# contact.net
KiCad netlist of a schematic drawn in EAGLE
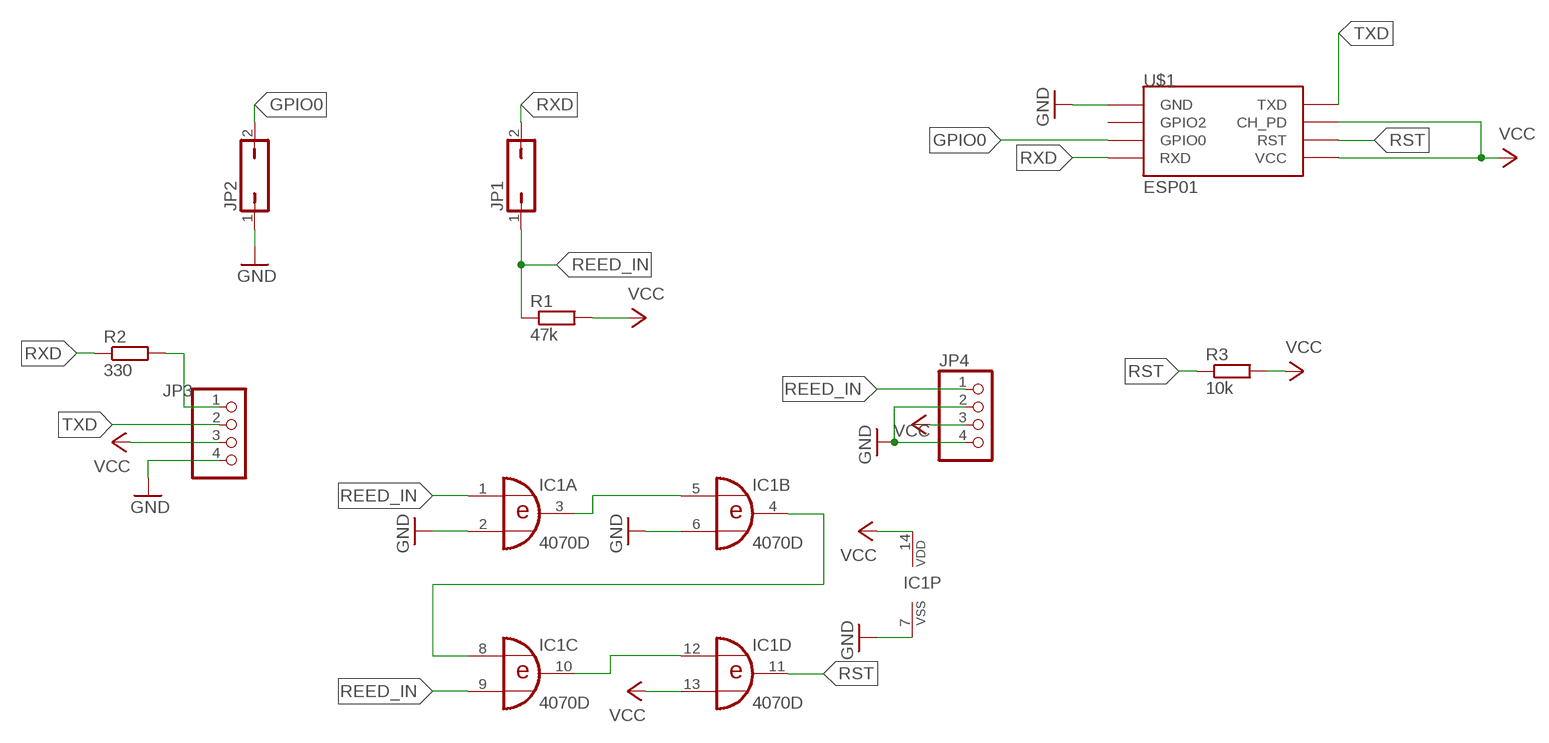
[diagram p0: schematic, sheet 1]

(export (version "E")
  (design (tool "Eeschema 10.0.6"))
  (components
    (comp (ref "IC1")
      (value "4070D")
      (footprint "eagle-import:SO14")
      (libsource (lib "eagle-import") (part "4070D"))
    )
    (comp (ref "JP1")
      (value "JP1Q")
      (footprint "eagle-import:JP1")
      (libsource (lib "eagle-import") (part "JP1Q"))
    )
    (comp (ref "JP2")
      (value "JP1Q")
      (footprint "eagle-import:JP1")
      (libsource (lib "eagle-import") (part "JP1Q"))
    )
    (comp (ref "JP3")
      (value "PINHD-1X4")
      (footprint "eagle-import:1X04")
      (libsource (lib "eagle-import") (part "PINHD-1X4"))
    )
    (comp (ref "JP4")
      (value "PINHD-1X4")
      (footprint "eagle-import:1X04")
      (libsource (lib "eagle-import") (part "PINHD-1X4"))
    )
    (comp (ref "R1")
      (value "47k")
      (footprint "eagle-import:R0805")
      (libsource (lib "eagle-import") (part "R-EU_R0805"))
    )
    (comp (ref "R2")
      (value "330")
      (footprint "eagle-import:R0805")
      (libsource (lib "eagle-import") (part "R-EU_R0805"))
    )
    (comp (ref "R3")
      (value "10k")
      (footprint "eagle-import:R0805")
      (libsource (lib "eagle-import") (part "R-EU_R0805"))
    )
    (comp (ref "U$1")
      (value "ESP01")
      (footprint "eagle-import:ESP01")
      (libsource (lib "eagle-import") (part "ESP01"))
    )
  )
  (nets
    (net (code "1") (name "GND") (class "Default")
      (node (ref "IC1") (pin "2") (pinfunction "I1_2") (pintype "input"))
      (node (ref "IC1") (pin "6") (pinfunction "I1_6") (pintype "input"))
      (node (ref "IC1") (pin "7") (pinfunction "VSS_7") (pintype "power_in"))
      (node (ref "JP2") (pin "1") (pinfunction "1_1") (pintype "passive"))
      (node (ref "JP3") (pin "4") (pinfunction "4_4") (pintype "passive"))
      (node (ref "JP4") (pin "2") (pinfunction "2_2") (pintype "passive"))
      (node (ref "JP4") (pin "4") (pinfunction "4_4") (pintype "passive"))
      (node (ref "U$1") (pin "GND") (pinfunction "GND_GND") (pintype "bidirectional"))
    )
    (net (code "2") (name "GPIO0") (class "Default")
      (node (ref "JP2") (pin "2") (pinfunction "2_2") (pintype "passive"))
      (node (ref "U$1") (pin "GPIO0") (pinfunction "GPIO0_GPIO0") (pintype "bidirectional"))
    )
    (net (code "3") (name "Net-(IC1A-O)") (class "Default")
      (node (ref "IC1") (pin "3") (pinfunction "O_3") (pintype "output"))
      (node (ref "IC1") (pin "5") (pinfunction "I0_5") (pintype "input"))
    )
    (net (code "4") (name "Net-(IC1B-O)") (class "Default")
      (node (ref "IC1") (pin "4") (pinfunction "O_4") (pintype "output"))
      (node (ref "IC1") (pin "8") (pinfunction "I0_8") (pintype "input"))
    )
    (net (code "5") (name "Net-(IC1C-O)") (class "Default")
      (node (ref "IC1") (pin "10") (pinfunction "O_10") (pintype "output"))
      (node (ref "IC1") (pin "12") (pinfunction "I0_12") (pintype "input"))
    )
    (net (code "6") (name "Net-(JP3-Pad1)") (class "Default")
      (node (ref "JP3") (pin "1") (pinfunction "1_1") (pintype "passive"))
      (node (ref "R2") (pin "2") (pinfunction "2_2") (pintype "passive"))
    )
    (net (code "7") (name "REED_IN") (class "Default")
      (node (ref "IC1") (pin "1") (pinfunction "I0_1") (pintype "input"))
      (node (ref "IC1") (pin "9") (pinfunction "I1_9") (pintype "input"))
      (node (ref "JP1") (pin "1") (pinfunction "1_1") (pintype "passive"))
      (node (ref "JP4") (pin "1") (pinfunction "1_1") (pintype "passive"))
      (node (ref "R1") (pin "1") (pinfunction "1_1") (pintype "passive"))
    )
    (net (code "8") (name "RST") (class "Default")
      (node (ref "IC1") (pin "11") (pinfunction "O_11") (pintype "output"))
      (node (ref "R3") (pin "1") (pinfunction "1_1") (pintype "passive"))
      (node (ref "U$1") (pin "RST") (pinfunction "RST_RST") (pintype "bidirectional"))
    )
    (net (code "9") (name "RXD") (class "Default")
      (node (ref "JP1") (pin "2") (pinfunction "2_2") (pintype "passive"))
      (node (ref "R2") (pin "1") (pinfunction "1_1") (pintype "passive"))
      (node (ref "U$1") (pin "RX") (pinfunction "RXD_RX") (pintype "bidirectional"))
    )
    (net (code "10") (name "TXD") (class "Default")
      (node (ref "JP3") (pin "2") (pinfunction "2_2") (pintype "passive"))
      (node (ref "U$1") (pin "TX") (pinfunction "TXD_TX") (pintype "bidirectional"))
    )
    (net (code "11") (name "VCC") (class "Default")
      (node (ref "IC1") (pin "13") (pinfunction "I1_13") (pintype "input"))
      (node (ref "IC1") (pin "14") (pinfunction "VDD_14") (pintype "power_in"))
      (node (ref "JP3") (pin "3") (pinfunction "3_3") (pintype "passive"))
      (node (ref "JP4") (pin "3") (pinfunction "3_3") (pintype "passive"))
      (node (ref "R1") (pin "2") (pinfunction "2_2") (pintype "passive"))
      (node (ref "R3") (pin "2") (pinfunction "2_2") (pintype "passive"))
      (node (ref "U$1") (pin "CH_PD") (pinfunction "CH_PD_CH_PD") (pintype "bidirectional"))
      (node (ref "U$1") (pin "VCC") (pinfunction "VCC_VCC") (pintype "bidirectional"))
    )
    (net (code "12") (name "unconnected-(U$1-PadGPIO2)") (class "Default")
      (node (ref "U$1") (pin "GPIO2") (pinfunction "GPIO2_GPIO2") (pintype "bidirectional"))
    )
  )
)
